# BLDC_4.net
KiCad netlist of a schematic drawn in Altium Designer
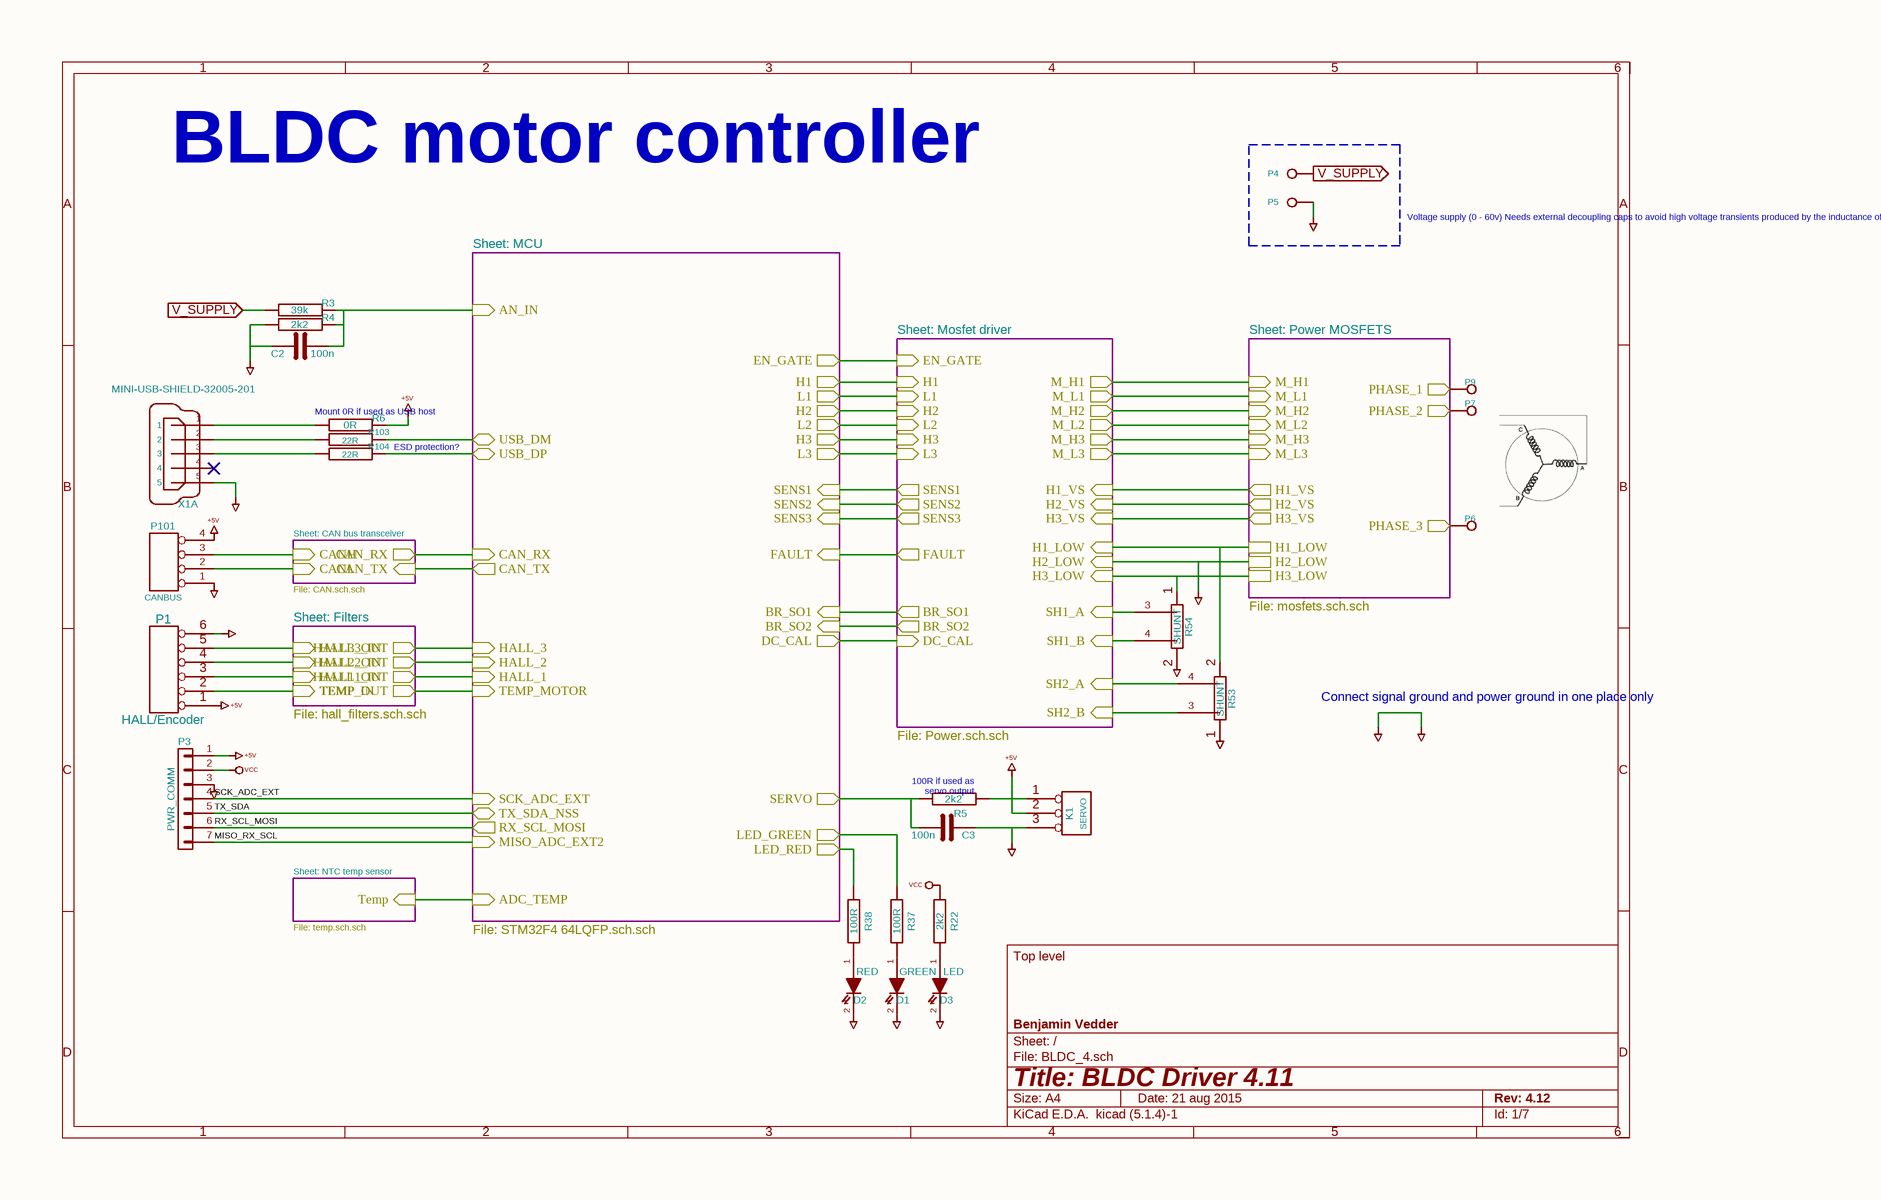
[diagram p0: BLDC_4.SchDoc]

(export (version "E")
  (design (tool "Eeschema 10.0.6"))
  (components
    (comp (ref "C2") (value "100n") (libsource (lib "*") (part "C-RESCUE-BLDC_4")))
    (comp (ref "C3") (value "100n") (libsource (lib "*") (part "C-RESCUE-BLDC_4")))
    (comp (ref "D1") (value "GREEN") (libsource (lib "*") (part "LED-RESCUE-BLDC_4")))
    (comp (ref "D2") (value "RED") (libsource (lib "*") (part "LED-RESCUE-BLDC_4")))
    (comp (ref "D3") (value "LED") (libsource (lib "*") (part "LED-RESCUE-BLDC_4")))
    (comp (ref "K1") (value "SERVO") (libsource (lib "*") (part "CONN_3")))
    (comp (ref "P1") (value "HALL/Encoder") (libsource (lib "*") (part "CONN_6")))
    (comp (ref "P3") (value "PWR_COMM") (libsource (lib "*") (part "CONN_01X07")))
    (comp (ref "P4") (value "IN+") (libsource (lib "*") (part "CONN_1")))
    (comp (ref "P5") (value "IN-") (libsource (lib "*") (part "CONN_1")))
    (comp (ref "P6") (value "MOTOR1") (libsource (lib "*") (part "CONN_1")))
    (comp (ref "P7") (value "MOTOR2") (libsource (lib "*") (part "CONN_1")))
    (comp (ref "P9") (value "MOTOR3") (libsource (lib "*") (part "CONN_1")))
    (comp (ref "P101") (value "CANBUS") (libsource (lib "*") (part "CONN_4")))
    (comp (ref "R3") (value "39k") (libsource (lib "*") (part "R-RESCUE-BLDC_4")))
    (comp (ref "R4") (value "2k2") (libsource (lib "*") (part "R-RESCUE-BLDC_4")))
    (comp (ref "R5") (value "2k2") (libsource (lib "") (part "R-RESCUE-BLDC_4_1")))
    (comp (ref "R6") (value "0R") (libsource (lib "*") (part "R-RESCUE-BLDC_4")))
    (comp (ref "R22") (value "2k2") (libsource (lib "*") (part "R-RESCUE-BLDC_4")))
    (comp (ref "R37") (value "100R") (libsource (lib "*") (part "R-RESCUE-BLDC_4")))
    (comp (ref "R38") (value "100R") (libsource (lib "*") (part "R-RESCUE-BLDC_4")))
    (comp (ref "R53") (value "SHUNT") (libsource (lib "") (part "SHUNT_1")))
    (comp (ref "R54") (value "SHUNT") (libsource (lib "*") (part "SHUNT")))
    (comp (ref "R103") (value "22R") (libsource (lib "") (part "R-RESCUE-BLDC_4_2")))
    (comp (ref "R104") (value "22R") (libsource (lib "") (part "R-RESCUE-BLDC_4_2")))
    (comp (ref "X1")
      (value "MINI-USB-SHIELD-32005-201")
      (libsource (lib "*") (part "MINI-USB-SCHIELD-32005-201"))
    )
  )
  (nets
    (net (code "1") (name "+5V") (class "Default")
      (node (ref "K1") (pin "2") (pinfunction "PM_2") (pintype "passive"))
      (node (ref "P1") (pin "1") (pinfunction "1_1") (pintype "passive"))
      (node (ref "P101") (pin "4") (pinfunction "P4_4") (pintype "passive"))
      (node (ref "P3") (pin "1") (pinfunction "P1_1") (pintype "passive"))
      (node (ref "R6") (pin "2") (pinfunction "2_2") (pintype "passive"))
    )
    (net (code "3") (name "/AN_IN") (class "Default")
      (node (ref "C2") (pin "2") (pinfunction "2_2") (pintype "passive"))
      (node (ref "R3") (pin "2") (pinfunction "2_2") (pintype "passive"))
      (node (ref "R4") (pin "2") (pinfunction "2_2") (pintype "passive"))
    )
    (net (code "6") (name "/CANH") (class "Default")
      (node (ref "P101") (pin "3") (pinfunction "P3_3") (pintype "passive"))
    )
    (net (code "7") (name "/CANL") (class "Default")
      (node (ref "P101") (pin "2") (pinfunction "P2_2") (pintype "passive"))
    )
    (net (code "14") (name "/H1_LOW") (class "Default")
      (node (ref "R53") (pin "2") (pinfunction "2_2") (pintype "passive"))
    )
    (net (code "19") (name "/H3_LOW") (class "Default")
      (node (ref "R54") (pin "1") (pinfunction "1_1") (pintype "passive"))
    )
    (net (code "21") (name "/HALL1_IN") (class "Default")
      (node (ref "P1") (pin "3") (pinfunction "3_3") (pintype "passive"))
    )
    (net (code "23") (name "/HALL2_IN") (class "Default")
      (node (ref "P1") (pin "4") (pinfunction "4_4") (pintype "passive"))
    )
    (net (code "25") (name "/HALL3_IN") (class "Default")
      (node (ref "P1") (pin "5") (pinfunction "5_5") (pintype "passive"))
    )
    (net (code "30") (name "/LED_GREEN") (class "Default")
      (node (ref "R37") (pin "2") (pinfunction "2_2") (pintype "passive"))
    )
    (net (code "31") (name "/LED_RED") (class "Default")
      (node (ref "R38") (pin "2") (pinfunction "2_2") (pintype "passive"))
    )
    (net (code "32") (name "/MISO_RX_SCL") (class "Default")
      (node (ref "P3") (pin "7") (pinfunction "P7_7") (pintype "passive"))
    )
    (net (code "39") (name "/PHASE_1") (class "Default")
      (node (ref "P9") (pin "1") (pinfunction "1_1") (pintype "passive"))
    )
    (net (code "40") (name "/PHASE_2") (class "Default")
      (node (ref "P7") (pin "1") (pinfunction "1_1") (pintype "passive"))
    )
    (net (code "41") (name "/PHASE_3") (class "Default")
      (node (ref "P6") (pin "1") (pinfunction "1_1") (pintype "passive"))
    )
    (net (code "42") (name "/RX_SCL_MOSI") (class "Default")
      (node (ref "P3") (pin "6") (pinfunction "P6_6") (pintype "passive"))
    )
    (net (code "43") (name "/SCK_ADC_EXT") (class "Default")
      (node (ref "P3") (pin "4") (pinfunction "P4_4") (pintype "passive"))
    )
    (net (code "47") (name "/SERVO") (class "Default")
      (node (ref "C3") (pin "2") (pinfunction "2_2") (pintype "passive"))
      (node (ref "R5") (pin "1") (pinfunction "1_1") (pintype "passive"))
    )
    (net (code "48") (name "/SH1_A") (class "Default")
      (node (ref "R54") (pin "3") (pinfunction "3_3") (pintype "passive"))
    )
    (net (code "49") (name "/SH1_B") (class "Default")
      (node (ref "R54") (pin "4") (pinfunction "4_4") (pintype "passive"))
    )
    (net (code "50") (name "/SH2_A") (class "Default")
      (node (ref "R53") (pin "4") (pinfunction "4_4") (pintype "passive"))
    )
    (net (code "51") (name "/SH2_B") (class "Default")
      (node (ref "R53") (pin "3") (pinfunction "3_3") (pintype "passive"))
    )
    (net (code "52") (name "/TEMP_IN") (class "Default")
      (node (ref "P1") (pin "2") (pinfunction "2_2") (pintype "passive"))
    )
    (net (code "54") (name "/TX_SDA") (class "Default")
      (node (ref "P3") (pin "5") (pinfunction "P5_5") (pintype "passive"))
    )
    (net (code "55") (name "/USB_DM") (class "Default")
      (node (ref "R103") (pin "1") (pinfunction "1_1") (pintype "passive"))
    )
    (net (code "56") (name "/USB_DP") (class "Default")
      (node (ref "R104") (pin "1") (pinfunction "1_1") (pintype "passive"))
    )
    (net (code "57") (name "/V_SUPPLY") (class "Default")
      (node (ref "P4") (pin "1") (pinfunction "1_1") (pintype "passive"))
      (node (ref "R3") (pin "1") (pinfunction "1_1") (pintype "passive"))
    )
    (net (code "58") (name "GND") (class "Default")
      (node (ref "C2") (pin "1") (pinfunction "1_1") (pintype "passive"))
      (node (ref "C3") (pin "1") (pinfunction "1_1") (pintype "passive"))
      (node (ref "D1") (pin "2") (pinfunction "K_2") (pintype "passive"))
      (node (ref "D2") (pin "2") (pinfunction "K_2") (pintype "passive"))
      (node (ref "D3") (pin "2") (pinfunction "K_2") (pintype "passive"))
      (node (ref "K1") (pin "3") (pinfunction "P3_3") (pintype "passive"))
      (node (ref "P1") (pin "6") (pinfunction "6_6") (pintype "passive"))
      (node (ref "P101") (pin "1") (pinfunction "P1_1") (pintype "passive"))
      (node (ref "P3") (pin "3") (pinfunction "P3_3") (pintype "passive"))
      (node (ref "P5") (pin "1") (pinfunction "1_1") (pintype "passive"))
      (node (ref "R4") (pin "1") (pinfunction "1_1") (pintype "passive"))
      (node (ref "R53") (pin "1") (pinfunction "1_1") (pintype "passive"))
      (node (ref "R54") (pin "2") (pinfunction "2_2") (pintype "passive"))
      (node (ref "X1") (pin "5") (pinfunction "5_5") (pintype "passive"))
    )
    (net (code "59") (name "Net-(D1-A)") (class "Default")
      (node (ref "D1") (pin "1") (pinfunction "A_1") (pintype "passive"))
      (node (ref "R37") (pin "1") (pinfunction "1_1") (pintype "passive"))
    )
    (net (code "60") (name "Net-(D2-A)") (class "Default")
      (node (ref "D2") (pin "1") (pinfunction "A_1") (pintype "passive"))
      (node (ref "R38") (pin "1") (pinfunction "1_1") (pintype "passive"))
    )
    (net (code "61") (name "Net-(D3-A)") (class "Default")
      (node (ref "D3") (pin "1") (pinfunction "A_1") (pintype "passive"))
      (node (ref "R22") (pin "1") (pinfunction "1_1") (pintype "passive"))
    )
    (net (code "62") (name "Net-(K1-P1)") (class "Default")
      (node (ref "K1") (pin "1") (pinfunction "P1_1") (pintype "passive"))
      (node (ref "R5") (pin "2") (pinfunction "2_2") (pintype "passive"))
    )
    (net (code "63") (name "Net-(R6-Pad1)") (class "Default")
      (node (ref "R6") (pin "1") (pinfunction "1_1") (pintype "passive"))
      (node (ref "X1") (pin "1") (pinfunction "1_1") (pintype "passive"))
    )
    (net (code "64") (name "Net-(R103-Pad2)") (class "Default")
      (node (ref "R103") (pin "2") (pinfunction "2_2") (pintype "passive"))
      (node (ref "X1") (pin "2") (pinfunction "2_2") (pintype "passive"))
    )
    (net (code "65") (name "Net-(R104-Pad2)") (class "Default")
      (node (ref "R104") (pin "2") (pinfunction "2_2") (pintype "passive"))
      (node (ref "X1") (pin "3") (pinfunction "3_3") (pintype "passive"))
    )
    (net (code "66") (name "VCC") (class "Default")
      (node (ref "P3") (pin "2") (pinfunction "P2_2") (pintype "passive"))
      (node (ref "R22") (pin "2") (pinfunction "2_2") (pintype "passive"))
    )
    (net (code "67") (name "unconnected-(X1-Pad4)") (class "Default")
      (node (ref "X1") (pin "4") (pinfunction "4_4") (pintype "passive+no_connect"))
    )
  )
)
